# Group_Project_PCB_Updated.net
KiCad netlist of a schematic drawn in EAGLE
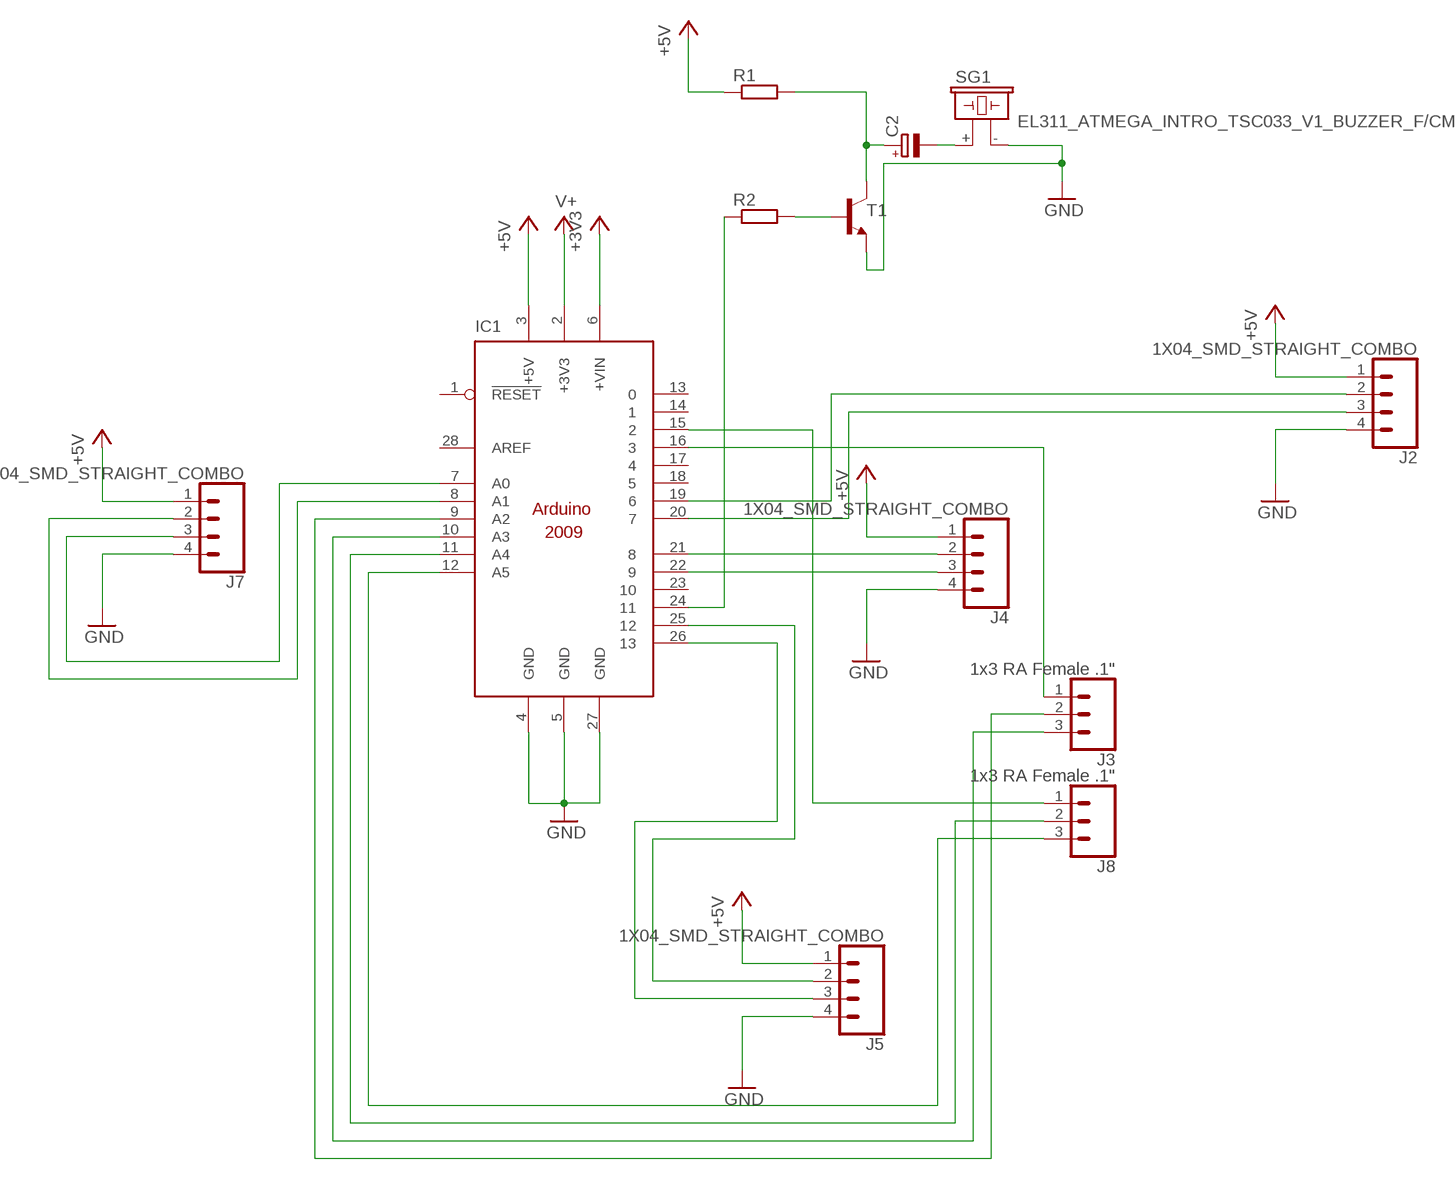
[diagram p0: schematic, sheet 1]

(export (version "E")
  (design (tool "Eeschema 10.0.6"))
  (components
    (comp (ref "C2")
      (value "RCL_CPOL-EUE3.5-8")
      (footprint "eagle-import:ELECTROLYTIC_CAP_RCL_E3,5-8")
      (libsource (lib "eagle-import") (part "RCL_CPOL-EUE3.5-8"))
    )
    (comp (ref "IC1")
      (value "ARDUINO2009_10")
      (footprint "eagle-import:ARDUINO2009")
      (libsource (lib "eagle-import") (part "ARDUINO2009_10"))
    )
    (comp (ref "J2")
      (value "1X04_SMD_STRAIGHT_COMBO")
      (footprint "eagle-import:1X04_LONGPADS")
      (libsource (lib "eagle-import") (part "CONN_04LONGPADS"))
    )
    (comp (ref "J3")
      (value "1x3 RA Female .1\"")
      (footprint "eagle-import:1X03_LONGPADS")
      (libsource (lib "eagle-import") (part "CONN_03LONGPADS"))
    )
    (comp (ref "J4")
      (value "1X04_SMD_STRAIGHT_COMBO")
      (footprint "eagle-import:1X04_LONGPADS")
      (libsource (lib "eagle-import") (part "CONN_04LONGPADS"))
    )
    (comp (ref "J5")
      (value "1X04_SMD_STRAIGHT_COMBO")
      (footprint "eagle-import:1X04_LONGPADS")
      (libsource (lib "eagle-import") (part "CONN_04LONGPADS"))
    )
    (comp (ref "J7")
      (value "1X04_SMD_STRAIGHT_COMBO")
      (footprint "eagle-import:1X04_LONGPADS")
      (libsource (lib "eagle-import") (part "CONN_04LONGPADS"))
    )
    (comp (ref "J8")
      (value "1x3 RA Female .1\"")
      (footprint "eagle-import:1X03_LONGPADS")
      (libsource (lib "eagle-import") (part "CONN_03LONGPADS"))
    )
    (comp (ref "R1")
      (value "R-EU_0207/10")
      (footprint "eagle-import:0207_10")
      (libsource (lib "eagle-import") (part "R-EU_0207/10"))
    )
    (comp (ref "R2")
      (value "R-EU_0207/10")
      (footprint "eagle-import:0207_10")
      (libsource (lib "eagle-import") (part "R-EU_0207/10"))
    )
    (comp (ref "SG1")
      (value "EL311_ATMEGA_INTRO_TSC033_V1_BUZZER_F/CM12P")
      (footprint "eagle-import:EL311_ATMEGA_INTRO_TSC033_V1_BUZZER_F_CM12P")
      (libsource (lib "eagle-import") (part "EL311_ATMEGA_INTRO_TSC033_V1_BUZZER_F/CM12P"))
    )
    (comp (ref "T1")
      (value "2N1613-NPN-TO92-EBC")
      (footprint "eagle-import:TO92-EBC")
      (libsource (lib "eagle-import") (part "-NPN-TO92-EBC2N1613"))
    )
  )
  (nets
    (net (code "1") (name "+3V3") (class "Default")
      (node (ref "IC1") (pin "6") (pinfunction "+VIN_6") (pintype "bidirectional"))
    )
    (net (code "2") (name "+5V") (class "Default")
      (node (ref "IC1") (pin "3") (pinfunction "+5V_3") (pintype "power_in"))
      (node (ref "J2") (pin "1") (pinfunction "1_1") (pintype "passive"))
      (node (ref "J4") (pin "1") (pinfunction "1_1") (pintype "passive"))
      (node (ref "J5") (pin "1") (pinfunction "1_1") (pintype "passive"))
      (node (ref "J7") (pin "1") (pinfunction "1_1") (pintype "passive"))
      (node (ref "R1") (pin "1") (pinfunction "1_1") (pintype "passive"))
    )
    (net (code "3") (name "GND") (class "Default")
      (node (ref "IC1") (pin "27") (pinfunction "GND_27") (pintype "power_in"))
      (node (ref "IC1") (pin "4") (pinfunction "GND_4") (pintype "power_in"))
      (node (ref "IC1") (pin "5") (pinfunction "GND_5") (pintype "power_in"))
      (node (ref "J2") (pin "4") (pinfunction "4_4") (pintype "passive"))
      (node (ref "J4") (pin "4") (pinfunction "4_4") (pintype "passive"))
      (node (ref "J5") (pin "4") (pinfunction "4_4") (pintype "passive"))
      (node (ref "J7") (pin "4") (pinfunction "4_4") (pintype "passive"))
      (node (ref "SG1") (pin "-") (pinfunction "2_-") (pintype "passive"))
      (node (ref "T1") (pin "E") (pinfunction "E_E") (pintype "passive"))
    )
    (net (code "4") (name "Net-(C2-Pad+)") (class "Default")
      (node (ref "C2") (pin "+") (pinfunction "+_+") (pintype "passive"))
      (node (ref "R1") (pin "2") (pinfunction "2_2") (pintype "passive"))
      (node (ref "T1") (pin "C") (pinfunction "C_C") (pintype "passive"))
    )
    (net (code "5") (name "Net-(IC1-2)") (class "Default")
      (node (ref "IC1") (pin "15") (pinfunction "2_15") (pintype "bidirectional"))
      (node (ref "J8") (pin "1") (pinfunction "1_1") (pintype "passive"))
    )
    (net (code "6") (name "Net-(IC1-3)") (class "Default")
      (node (ref "IC1") (pin "16") (pinfunction "3_16") (pintype "bidirectional"))
      (node (ref "J3") (pin "1") (pinfunction "1_1") (pintype "passive"))
    )
    (net (code "7") (name "Net-(IC1-6)") (class "Default")
      (node (ref "IC1") (pin "19") (pinfunction "6_19") (pintype "bidirectional"))
      (node (ref "J2") (pin "2") (pinfunction "2_2") (pintype "passive"))
    )
    (net (code "8") (name "Net-(IC1-7)") (class "Default")
      (node (ref "IC1") (pin "20") (pinfunction "7_20") (pintype "bidirectional"))
      (node (ref "J2") (pin "3") (pinfunction "3_3") (pintype "passive"))
    )
    (net (code "9") (name "Net-(IC1-8)") (class "Default")
      (node (ref "IC1") (pin "21") (pinfunction "8_21") (pintype "bidirectional"))
      (node (ref "J4") (pin "2") (pinfunction "2_2") (pintype "passive"))
    )
    (net (code "10") (name "Net-(IC1-9)") (class "Default")
      (node (ref "IC1") (pin "22") (pinfunction "9_22") (pintype "bidirectional"))
      (node (ref "J4") (pin "3") (pinfunction "3_3") (pintype "passive"))
    )
    (net (code "11") (name "Net-(IC1-11)") (class "Default")
      (node (ref "IC1") (pin "24") (pinfunction "11_24") (pintype "bidirectional"))
      (node (ref "R2") (pin "1") (pinfunction "1_1") (pintype "passive"))
    )
    (net (code "12") (name "Net-(IC1-12)") (class "Default")
      (node (ref "IC1") (pin "25") (pinfunction "12_25") (pintype "bidirectional"))
      (node (ref "J5") (pin "2") (pinfunction "2_2") (pintype "passive"))
    )
    (net (code "13") (name "Net-(IC1-13)") (class "Default")
      (node (ref "IC1") (pin "26") (pinfunction "13_26") (pintype "bidirectional"))
      (node (ref "J5") (pin "3") (pinfunction "3_3") (pintype "passive"))
    )
    (net (code "14") (name "Net-(IC1-A0)") (class "Default")
      (node (ref "IC1") (pin "7") (pinfunction "A0_7") (pintype "bidirectional"))
      (node (ref "J7") (pin "3") (pinfunction "3_3") (pintype "passive"))
    )
    (net (code "15") (name "Net-(IC1-A1)") (class "Default")
      (node (ref "IC1") (pin "8") (pinfunction "A1_8") (pintype "bidirectional"))
      (node (ref "J7") (pin "2") (pinfunction "2_2") (pintype "passive"))
    )
    (net (code "16") (name "Net-(IC1-A2)") (class "Default")
      (node (ref "IC1") (pin "9") (pinfunction "A2_9") (pintype "bidirectional"))
      (node (ref "J3") (pin "2") (pinfunction "2_2") (pintype "passive"))
    )
    (net (code "17") (name "Net-(IC1-A3)") (class "Default")
      (node (ref "IC1") (pin "10") (pinfunction "A3_10") (pintype "bidirectional"))
      (node (ref "J3") (pin "3") (pinfunction "3_3") (pintype "passive"))
    )
    (net (code "18") (name "Net-(IC1-A4)") (class "Default")
      (node (ref "IC1") (pin "11") (pinfunction "A4_11") (pintype "bidirectional"))
      (node (ref "J8") (pin "2") (pinfunction "2_2") (pintype "passive"))
    )
    (net (code "19") (name "Net-(IC1-A5)") (class "Default")
      (node (ref "IC1") (pin "12") (pinfunction "A5_12") (pintype "bidirectional"))
      (node (ref "J8") (pin "3") (pinfunction "3_3") (pintype "passive"))
    )
    (net (code "20") (name "Net-(R2-Pad2)") (class "Default")
      (node (ref "R2") (pin "2") (pinfunction "2_2") (pintype "passive"))
      (node (ref "T1") (pin "B") (pinfunction "B_B") (pintype "passive"))
    )
    (net (code "21") (name "Net-(SG1-1)") (class "Default")
      (node (ref "C2") (pin "-") (pinfunction "-_-") (pintype "passive"))
      (node (ref "SG1") (pin "+") (pinfunction "1_+") (pintype "passive"))
    )
    (net (code "22") (name "V+") (class "Default")
      (node (ref "IC1") (pin "2") (pinfunction "+3V3_2") (pintype "power_in"))
    )
    (net (code "23") (name "unconnected-(IC1-0-Pad13)") (class "Default")
      (node (ref "IC1") (pin "13") (pinfunction "0_13") (pintype "bidirectional"))
    )
    (net (code "24") (name "unconnected-(IC1-1-Pad14)") (class "Default")
      (node (ref "IC1") (pin "14") (pinfunction "1_14") (pintype "bidirectional"))
    )
    (net (code "25") (name "unconnected-(IC1-4-Pad17)") (class "Default")
      (node (ref "IC1") (pin "17") (pinfunction "4_17") (pintype "bidirectional"))
    )
    (net (code "26") (name "unconnected-(IC1-5-Pad18)") (class "Default")
      (node (ref "IC1") (pin "18") (pinfunction "5_18") (pintype "bidirectional"))
    )
    (net (code "27") (name "unconnected-(IC1-10-Pad23)") (class "Default")
      (node (ref "IC1") (pin "23") (pinfunction "10_23") (pintype "bidirectional"))
    )
    (net (code "28") (name "unconnected-(IC1-AREF-Pad28)") (class "Default")
      (node (ref "IC1") (pin "28") (pinfunction "AREF_28") (pintype "bidirectional"))
    )
    (net (code "29") (name "unconnected-(IC1-~{RESET}-Pad1)") (class "Default")
      (node (ref "IC1") (pin "1") (pinfunction "~{RESET}_1") (pintype "bidirectional"))
    )
  )
)
